# water_level_aq.net
KiCad netlist of a schematic drawn in EAGLE
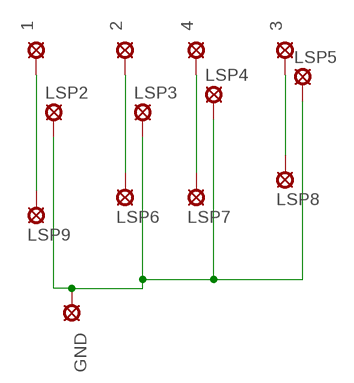
[diagram p0: schematic, sheet 1]

(export (version "E")
  (design (tool "Eeschema 10.0.6"))
  (components
    (comp (ref "1")
      (value "SE13")
      (footprint "eagle-import:SE13")
      (libsource (lib "eagle-import") (part "SE13"))
    )
    (comp (ref "2")
      (value "SE13")
      (footprint "eagle-import:SE13")
      (libsource (lib "eagle-import") (part "SE13"))
    )
    (comp (ref "3")
      (value "SE13")
      (footprint "eagle-import:SE13")
      (libsource (lib "eagle-import") (part "SE13"))
    )
    (comp (ref "4")
      (value "SE13")
      (footprint "eagle-import:SE13")
      (libsource (lib "eagle-import") (part "SE13"))
    )
    (comp (ref "GND")
      (value "SE13")
      (footprint "eagle-import:SE13")
      (libsource (lib "eagle-import") (part "SE13"))
    )
    (comp (ref "LSP2")
      (value "MCS10B")
      (footprint "eagle-import:MCS10B")
      (libsource (lib "eagle-import") (part "MCS10B"))
    )
    (comp (ref "LSP3")
      (value "MCS10B")
      (footprint "eagle-import:MCS10B")
      (libsource (lib "eagle-import") (part "MCS10B"))
    )
    (comp (ref "LSP4")
      (value "MCS10B")
      (footprint "eagle-import:MCS10B")
      (libsource (lib "eagle-import") (part "MCS10B"))
    )
    (comp (ref "LSP5")
      (value "MCS10B")
      (footprint "eagle-import:MCS10B")
      (libsource (lib "eagle-import") (part "MCS10B"))
    )
    (comp (ref "LSP6")
      (value "MCS10B")
      (footprint "eagle-import:MCS10B")
      (libsource (lib "eagle-import") (part "MCS10B"))
    )
    (comp (ref "LSP7")
      (value "MCS10B")
      (footprint "eagle-import:MCS10B")
      (libsource (lib "eagle-import") (part "MCS10B"))
    )
    (comp (ref "LSP8")
      (value "MCS10B")
      (footprint "eagle-import:MCS10B")
      (libsource (lib "eagle-import") (part "MCS10B"))
    )
    (comp (ref "LSP9")
      (value "MCS10B")
      (footprint "eagle-import:MCS10B")
      (libsource (lib "eagle-import") (part "MCS10B"))
    )
  )
  (nets
    (net (code "1") (name "Net-(1-PadMP)") (class "Default")
      (node (ref "1") (pin "MP") (pinfunction "MP_MP") (pintype "passive"))
      (node (ref "LSP9") (pin "MP") (pinfunction "MP_MP") (pintype "passive"))
    )
    (net (code "2") (name "Net-(2-PadMP)") (class "Default")
      (node (ref "2") (pin "MP") (pinfunction "MP_MP") (pintype "passive"))
      (node (ref "LSP6") (pin "MP") (pinfunction "MP_MP") (pintype "passive"))
    )
    (net (code "3") (name "Net-(3-PadMP)") (class "Default")
      (node (ref "3") (pin "MP") (pinfunction "MP_MP") (pintype "passive"))
      (node (ref "LSP8") (pin "MP") (pinfunction "MP_MP") (pintype "passive"))
    )
    (net (code "4") (name "Net-(4-PadMP)") (class "Default")
      (node (ref "4") (pin "MP") (pinfunction "MP_MP") (pintype "passive"))
      (node (ref "LSP7") (pin "MP") (pinfunction "MP_MP") (pintype "passive"))
    )
    (net (code "5") (name "Net-(GND-PadMP)") (class "Default")
      (node (ref "GND") (pin "MP") (pinfunction "MP_MP") (pintype "passive"))
      (node (ref "LSP2") (pin "MP") (pinfunction "MP_MP") (pintype "passive"))
      (node (ref "LSP3") (pin "MP") (pinfunction "MP_MP") (pintype "passive"))
      (node (ref "LSP4") (pin "MP") (pinfunction "MP_MP") (pintype "passive"))
      (node (ref "LSP5") (pin "MP") (pinfunction "MP_MP") (pintype "passive"))
    )
  )
)
